# Helicopter_Control_Board.net
KiCad netlist of a schematic drawn in EAGLE
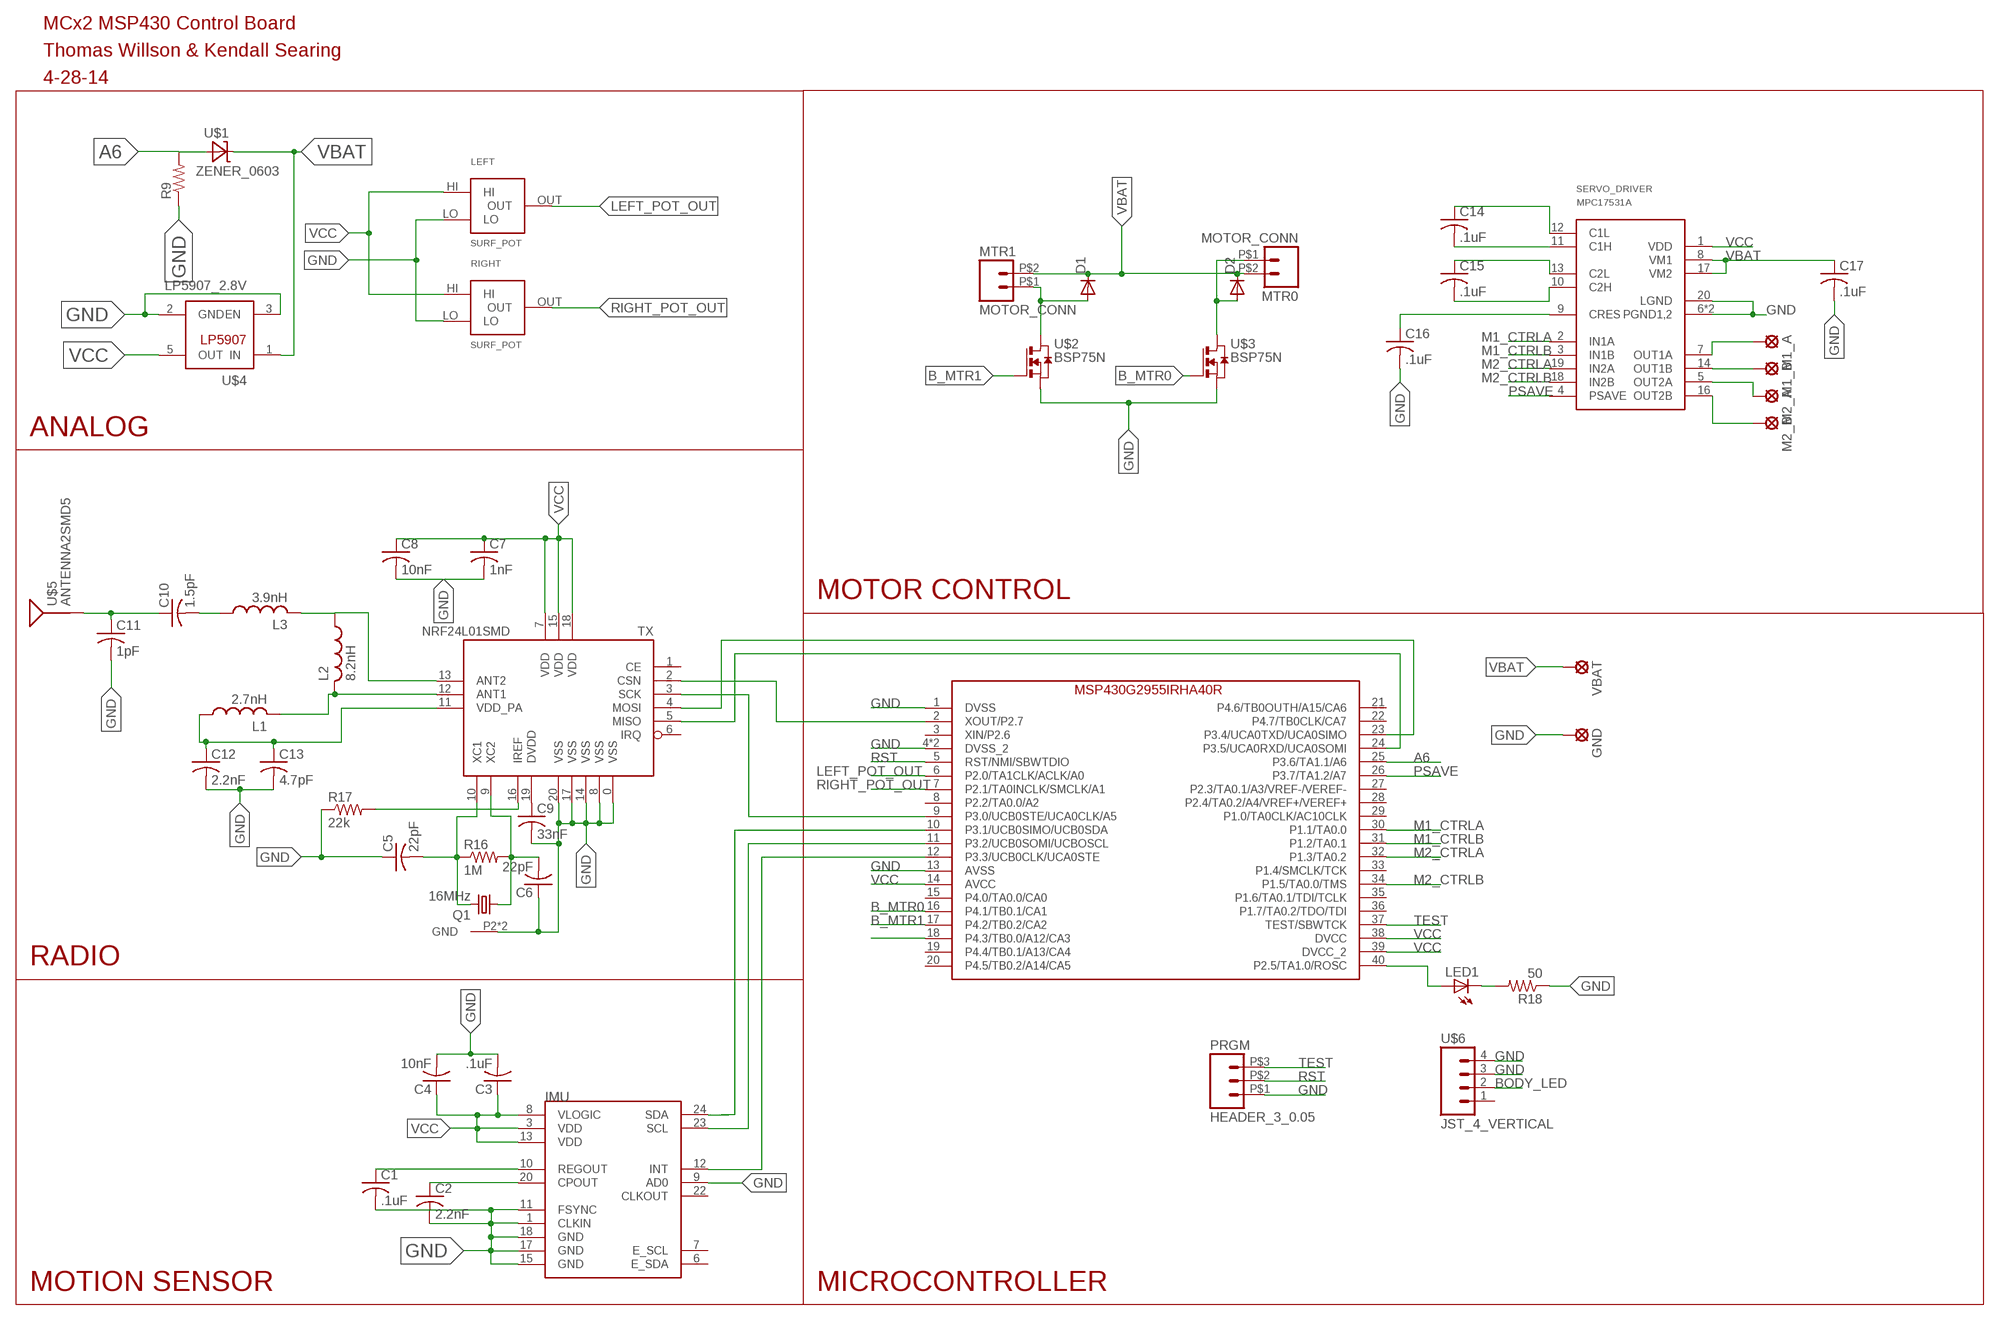
[diagram p0: schematic, sheet 1]

(export (version "E")
  (design (tool "Eeschema 10.0.6"))
  (components
    (comp (ref "C1")
      (value ".1uF")
      (footprint "eagle-import:C0402")
      (libsource (lib "eagle-import") (part "C-USC0402"))
    )
    (comp (ref "C2")
      (value "2.2nF")
      (footprint "eagle-import:C0402")
      (libsource (lib "eagle-import") (part "C-USC0402"))
    )
    (comp (ref "C3")
      (value ".1uF")
      (footprint "eagle-import:C0402")
      (libsource (lib "eagle-import") (part "C-USC0402"))
    )
    (comp (ref "C4")
      (value "10nF")
      (footprint "eagle-import:C0402")
      (libsource (lib "eagle-import") (part "C-USC0402"))
    )
    (comp (ref "C5")
      (value "22pF")
      (footprint "eagle-import:C0402")
      (libsource (lib "eagle-import") (part "C-USC0402"))
    )
    (comp (ref "C6")
      (value "22pF")
      (footprint "eagle-import:C0402")
      (libsource (lib "eagle-import") (part "C-USC0402"))
    )
    (comp (ref "C7")
      (value "1nF")
      (footprint "eagle-import:C0402")
      (libsource (lib "eagle-import") (part "C-USC0402"))
    )
    (comp (ref "C8")
      (value "10nF")
      (footprint "eagle-import:C0402")
      (libsource (lib "eagle-import") (part "C-USC0402"))
    )
    (comp (ref "C9")
      (value "33nF")
      (footprint "eagle-import:C0402")
      (libsource (lib "eagle-import") (part "C-USC0402"))
    )
    (comp (ref "C10")
      (value "1.5pF")
      (footprint "eagle-import:C0402")
      (libsource (lib "eagle-import") (part "C-USC0402"))
    )
    (comp (ref "C11")
      (value "1pF")
      (footprint "eagle-import:C0402")
      (libsource (lib "eagle-import") (part "C-USC0402"))
    )
    (comp (ref "C12")
      (value "2.2nF")
      (footprint "eagle-import:C0402")
      (libsource (lib "eagle-import") (part "C-USC0402"))
    )
    (comp (ref "C13")
      (value "4.7pF")
      (footprint "eagle-import:C0402")
      (libsource (lib "eagle-import") (part "C-USC0402"))
    )
    (comp (ref "C14")
      (value ".1uF")
      (footprint "eagle-import:C0402")
      (libsource (lib "eagle-import") (part "C-USC0402"))
    )
    (comp (ref "C15")
      (value ".1uF")
      (footprint "eagle-import:C0402")
      (libsource (lib "eagle-import") (part "C-USC0402"))
    )
    (comp (ref "C16")
      (value ".1uF")
      (footprint "eagle-import:C0402")
      (libsource (lib "eagle-import") (part "C-USC0402"))
    )
    (comp (ref "C17")
      (value ".1uF")
      (footprint "eagle-import:C0402")
      (libsource (lib "eagle-import") (part "C-USC0402"))
    )
    (comp (ref "D1")
      (value "DIODESMA")
      (footprint "eagle-import:SMA-DIODE")
      (libsource (lib "eagle-import") (part "DIODESMA"))
    )
    (comp (ref "D2")
      (value "DIODESMA")
      (footprint "eagle-import:SMA-DIODE")
      (libsource (lib "eagle-import") (part "DIODESMA"))
    )
    (comp (ref "GND")
      (value "LSP10")
      (footprint "eagle-import:LSP10")
      (libsource (lib "eagle-import") (part "LSP10"))
    )
    (comp (ref "IMU")
      (value "MPU-9150QFN-24-NP")
      (footprint "eagle-import:QFN-24-NP")
      (libsource (lib "eagle-import") (part "MPU-9150QFN-24-NP"))
    )
    (comp (ref "L1")
      (value "2.7nH")
      (footprint "eagle-import:R0402")
      (libsource (lib "eagle-import") (part "L-US"))
    )
    (comp (ref "L2")
      (value "8.2nH")
      (footprint "eagle-import:R0402")
      (libsource (lib "eagle-import") (part "L-US"))
    )
    (comp (ref "L3")
      (value "3.9nH")
      (footprint "eagle-import:R0402")
      (libsource (lib "eagle-import") (part "L-US"))
    )
    (comp (ref "LED1")
      (value "LED-BLUE0603")
      (footprint "eagle-import:LED-0603")
      (libsource (lib "eagle-import") (part "LED-BLUE0603"))
    )
    (comp (ref "LEFT")
      (value "SURF_POT")
      (footprint "eagle-import:SURF_POT")
      (libsource (lib "eagle-import") (part "SURF_POT"))
    )
    (comp (ref "M1_A")
      (value "LSP10")
      (footprint "eagle-import:LSP10")
      (libsource (lib "eagle-import") (part "LSP10"))
    )
    (comp (ref "M1_B")
      (value "LSP10")
      (footprint "eagle-import:LSP10")
      (libsource (lib "eagle-import") (part "LSP10"))
    )
    (comp (ref "M2_A")
      (value "LSP10")
      (footprint "eagle-import:LSP10")
      (libsource (lib "eagle-import") (part "LSP10"))
    )
    (comp (ref "M2_B")
      (value "LSP10")
      (footprint "eagle-import:LSP10")
      (libsource (lib "eagle-import") (part "LSP10"))
    )
    (comp (ref "MTR0")
      (value "MOTOR_CONN")
      (footprint "eagle-import:MOTOR_CONN")
      (libsource (lib "eagle-import") (part "MOTOR_CONN"))
    )
    (comp (ref "MTR1")
      (value "MOTOR_CONN")
      (footprint "eagle-import:MOTOR_CONN")
      (libsource (lib "eagle-import") (part "MOTOR_CONN"))
    )
    (comp (ref "PRGM")
      (value "HEADER_3_0.05")
      (footprint "eagle-import:HEADER_3_.05")
      (libsource (lib "eagle-import") (part "HEADER_3_0.05"))
    )
    (comp (ref "Q1")
      (value "16MHz")
      (footprint "eagle-import:TXC-4SMD")
      (libsource (lib "eagle-import") (part "CRYSTAL_16MHZ_12PF_SMD"))
    )
    (comp (ref "R9")
      (value "R-US_R0402")
      (footprint "eagle-import:R0402")
      (libsource (lib "eagle-import") (part "R-US_R0402"))
    )
    (comp (ref "R16")
      (value "1M")
      (footprint "eagle-import:R0402")
      (libsource (lib "eagle-import") (part "R-US_R0402"))
    )
    (comp (ref "R17")
      (value "22k")
      (footprint "eagle-import:R0402")
      (libsource (lib "eagle-import") (part "R-US_R0402"))
    )
    (comp (ref "R18")
      (value "50")
      (footprint "eagle-import:R0603")
      (libsource (lib "eagle-import") (part "R-US_R0603"))
    )
    (comp (ref "RIGHT")
      (value "SURF_POT")
      (footprint "eagle-import:SURF_POT")
      (libsource (lib "eagle-import") (part "SURF_POT"))
    )
    (comp (ref "SERVO_DRIVER")
      (value "MPC17531A")
      (footprint "eagle-import:SSOP_20")
      (libsource (lib "eagle-import") (part "MPC17531A"))
    )
    (comp (ref "TX")
      (value "NRF24L01SMD")
      (footprint "eagle-import:QFN20")
      (libsource (lib "eagle-import") (part "NRF24L01SMD"))
    )
    (comp (ref "U$1")
      (value "ZENER_0603")
      (footprint "eagle-import:ZENER_0603")
      (libsource (lib "eagle-import") (part "ZENER_0603"))
    )
    (comp (ref "U$2")
      (value "BSP75N")
      (footprint "eagle-import:PG-SOT-223")
      (libsource (lib "eagle-import") (part "BSP75N"))
    )
    (comp (ref "U$3")
      (value "BSP75N")
      (footprint "eagle-import:PG-SOT-223")
      (libsource (lib "eagle-import") (part "BSP75N"))
    )
    (comp (ref "U$4")
      (value "LP5907_2.8V")
      (footprint "eagle-import:SOT23-DBV")
      (libsource (lib "eagle-import") (part "LP5907"))
    )
    (comp (ref "U$5")
      (value "ANTENNA2SMD5")
      (footprint "eagle-import:ANTENNA-CHIP5")
      (libsource (lib "eagle-import") (part "ANTENNA2SMD5"))
    )
    (comp (ref "U$6")
      (value "JST_4_VERTICAL")
      (footprint "eagle-import:JST-4-SMD-VERT-1.0MM")
      (libsource (lib "eagle-import") (part "JST_4_VERTICAL"))
    )
    (comp (ref "U$8")
      (value "G2955IRHA40R")
      (footprint "eagle-import:RHA40")
      (libsource (lib "eagle-import") (part "G2955IRHA40R"))
    )
    (comp (ref "VBAT")
      (value "LSP10")
      (footprint "eagle-import:LSP10")
      (libsource (lib "eagle-import") (part "LSP10"))
    )
  )
  (nets
    (net (code "1") (name "/BODY_LED") (class "Default")
      (node (ref "U$6") (pin "2") (pinfunction "2_2") (pintype "passive"))
      (node (ref "U$8") (pin "18") (pinfunction "P4.3/TB0.0/A12/CA3_18") (pintype "bidirectional"))
    )
    (net (code "2") (name "/M1_CTRLA") (class "Default")
      (node (ref "SERVO_DRIVER") (pin "2") (pinfunction "IN1A_2") (pintype "bidirectional"))
      (node (ref "U$8") (pin "30") (pinfunction "P1.1/TA0.0_30") (pintype "bidirectional"))
    )
    (net (code "3") (name "/M1_CTRLB") (class "Default")
      (node (ref "SERVO_DRIVER") (pin "3") (pinfunction "IN1B_3") (pintype "bidirectional"))
      (node (ref "U$8") (pin "31") (pinfunction "P1.2/TA0.1_31") (pintype "bidirectional"))
    )
    (net (code "4") (name "/M2_CTRLA") (class "Default")
      (node (ref "SERVO_DRIVER") (pin "19") (pinfunction "IN2A_19") (pintype "bidirectional"))
      (node (ref "U$8") (pin "32") (pinfunction "P1.3/TA0.2_32") (pintype "bidirectional"))
    )
    (net (code "5") (name "/M2_CTRLB") (class "Default")
      (node (ref "SERVO_DRIVER") (pin "18") (pinfunction "IN2B_18") (pintype "bidirectional"))
      (node (ref "U$8") (pin "34") (pinfunction "P1.5/TA0.0/TMS_34") (pintype "bidirectional"))
    )
    (net (code "6") (name "/N$20") (class "Default")
      (node (ref "IMU") (pin "24") (pinfunction "SDA_24") (pintype "bidirectional"))
      (node (ref "U$8") (pin "10") (pinfunction "P3.1/UCB0SIMO/UCB0SDA_10") (pintype "bidirectional"))
    )
    (net (code "7") (name "/PSAVE") (class "Default")
      (node (ref "SERVO_DRIVER") (pin "4") (pinfunction "PSAVE_4") (pintype "bidirectional"))
      (node (ref "U$8") (pin "26") (pinfunction "P3.7/TA1.2/A7_26") (pintype "bidirectional"))
    )
    (net (code "8") (name "/RST") (class "Default")
      (node (ref "PRGM") (pin "P$2") (pinfunction "2_P$2") (pintype "passive"))
      (node (ref "U$8") (pin "5") (pinfunction "RST/NMI/SBWTDIO_5") (pintype "bidirectional"))
    )
    (net (code "9") (name "/TEST") (class "Default")
      (node (ref "PRGM") (pin "P$3") (pinfunction "3_P$3") (pintype "passive"))
      (node (ref "U$8") (pin "37") (pinfunction "TEST/SBWTCK_37") (pintype "bidirectional"))
    )
    (net (code "10") (name "A6") (class "Default")
      (node (ref "R9") (pin "2") (pinfunction "2_2") (pintype "passive"))
      (node (ref "U$1") (pin "A") (pinfunction "A_A") (pintype "passive"))
      (node (ref "U$8") (pin "25") (pinfunction "P3.6/TA1.1/A6_25") (pintype "bidirectional"))
    )
    (net (code "11") (name "B_MTR0") (class "Default")
      (node (ref "U$3") (pin "1") (pinfunction "G_1") (pintype "passive"))
      (node (ref "U$8") (pin "16") (pinfunction "P4.1/TB0.1/CA1_16") (pintype "bidirectional"))
    )
    (net (code "12") (name "B_MTR1") (class "Default")
      (node (ref "U$2") (pin "1") (pinfunction "G_1") (pintype "passive"))
      (node (ref "U$8") (pin "17") (pinfunction "P4.2/TB0.2/CA2_17") (pintype "bidirectional"))
    )
    (net (code "13") (name "GND") (class "Default")
      (node (ref "C1") (pin "2") (pinfunction "2_2") (pintype "passive"))
      (node (ref "C11") (pin "2") (pinfunction "2_2") (pintype "passive"))
      (node (ref "C12") (pin "2") (pinfunction "2_2") (pintype "passive"))
      (node (ref "C13") (pin "2") (pinfunction "2_2") (pintype "passive"))
      (node (ref "C16") (pin "2") (pinfunction "2_2") (pintype "passive"))
      (node (ref "C17") (pin "2") (pinfunction "2_2") (pintype "passive"))
      (node (ref "C2") (pin "2") (pinfunction "2_2") (pintype "passive"))
      (node (ref "C3") (pin "2") (pinfunction "2_2") (pintype "passive"))
      (node (ref "C4") (pin "2") (pinfunction "2_2") (pintype "passive"))
      (node (ref "C5") (pin "1") (pinfunction "1_1") (pintype "passive"))
      (node (ref "C6") (pin "1") (pinfunction "1_1") (pintype "passive"))
      (node (ref "C7") (pin "2") (pinfunction "2_2") (pintype "passive"))
      (node (ref "C8") (pin "2") (pinfunction "2_2") (pintype "passive"))
      (node (ref "C9") (pin "2") (pinfunction "2_2") (pintype "passive"))
      (node (ref "GND") (pin "MP") (pinfunction "MP_MP") (pintype "passive"))
      (node (ref "IMU") (pin "1") (pinfunction "CLKIN_1") (pintype "bidirectional"))
      (node (ref "IMU") (pin "11") (pinfunction "FSYNC_11") (pintype "bidirectional"))
      (node (ref "IMU") (pin "15") (pinfunction "GND_15") (pintype "bidirectional"))
      (node (ref "IMU") (pin "17") (pinfunction "GND_17") (pintype "bidirectional"))
      (node (ref "IMU") (pin "18") (pinfunction "GND_18") (pintype "bidirectional"))
      (node (ref "IMU") (pin "9") (pinfunction "AD0_9") (pintype "bidirectional"))
      (node (ref "LEFT") (pin "LO") (pinfunction "LO_LO") (pintype "bidirectional"))
      (node (ref "PRGM") (pin "P$1") (pinfunction "1_P$1") (pintype "passive"))
      (node (ref "Q1") (pin "P2") (pinfunction "GND_P2") (pintype "bidirectional"))
      (node (ref "Q1") (pin "P4") (pinfunction "GND_P4") (pintype "bidirectional"))
      (node (ref "R17") (pin "1") (pinfunction "1_1") (pintype "passive"))
      (node (ref "R18") (pin "1") (pinfunction "1_1") (pintype "passive"))
      (node (ref "R9") (pin "1") (pinfunction "1_1") (pintype "passive"))
      (node (ref "RIGHT") (pin "LO") (pinfunction "LO_LO") (pintype "bidirectional"))
      (node (ref "SERVO_DRIVER") (pin "15") (pinfunction "PGND1,2_15") (pintype "bidirectional"))
      (node (ref "SERVO_DRIVER") (pin "20") (pinfunction "LGND_20") (pintype "bidirectional"))
      (node (ref "SERVO_DRIVER") (pin "6") (pinfunction "PGND1,2_6") (pintype "bidirectional"))
      (node (ref "TX") (pin "0") (pinfunction "VSS_0") (pintype "power_in"))
      (node (ref "TX") (pin "14") (pinfunction "VSS_14") (pintype "power_in"))
      (node (ref "TX") (pin "17") (pinfunction "VSS_17") (pintype "power_in"))
      (node (ref "TX") (pin "20") (pinfunction "VSS_20") (pintype "power_in"))
      (node (ref "TX") (pin "8") (pinfunction "VSS_8") (pintype "power_in"))
      (node (ref "U$2") (pin "3") (pinfunction "S_3") (pintype "passive"))
      (node (ref "U$2") (pin "4") (pinfunction "S_4") (pintype "passive"))
      (node (ref "U$3") (pin "3") (pinfunction "S_3") (pintype "passive"))
      (node (ref "U$3") (pin "4") (pinfunction "S_4") (pintype "passive"))
      (node (ref "U$4") (pin "2") (pinfunction "GND_2") (pintype "bidirectional"))
      (node (ref "U$4") (pin "3") (pinfunction "EN_3") (pintype "bidirectional"))
      (node (ref "U$6") (pin "3") (pinfunction "3_3") (pintype "passive"))
      (node (ref "U$6") (pin "4") (pinfunction "4_4") (pintype "passive"))
      (node (ref "U$8") (pin "1") (pinfunction "DVSS_1") (pintype "bidirectional"))
      (node (ref "U$8") (pin "13") (pinfunction "AVSS_13") (pintype "bidirectional"))
      (node (ref "U$8") (pin "4") (pinfunction "DVSS_2_4") (pintype "bidirectional"))
      (node (ref "U$8") (pin "TP") (pinfunction "DVSS_2_TP") (pintype "bidirectional"))
    )
    (net (code "14") (name "LEFT_POT_OUT") (class "Default")
      (node (ref "LEFT") (pin "OUT") (pinfunction "OUT_OUT") (pintype "bidirectional"))
      (node (ref "U$8") (pin "6") (pinfunction "P2.0/TA1CLK/ACLK/A0_6") (pintype "bidirectional"))
    )
    (net (code "15") (name "Net-(C10-Pad2)") (class "Default")
      (node (ref "C10") (pin "2") (pinfunction "2_2") (pintype "passive"))
      (node (ref "L3") (pin "1") (pinfunction "1_1") (pintype "passive"))
    )
    (net (code "16") (name "Net-(IMU-CPOUT)") (class "Default")
      (node (ref "C2") (pin "1") (pinfunction "1_1") (pintype "passive"))
      (node (ref "IMU") (pin "20") (pinfunction "CPOUT_20") (pintype "bidirectional"))
    )
    (net (code "17") (name "Net-(IMU-INT)") (class "Default")
      (node (ref "IMU") (pin "12") (pinfunction "INT_12") (pintype "bidirectional"))
      (node (ref "U$8") (pin "12") (pinfunction "P3.3/UCB0CLK/UCA0STE_12") (pintype "bidirectional"))
    )
    (net (code "18") (name "Net-(IMU-REGOUT)") (class "Default")
      (node (ref "C1") (pin "1") (pinfunction "1_1") (pintype "passive"))
      (node (ref "IMU") (pin "10") (pinfunction "REGOUT_10") (pintype "bidirectional"))
    )
    (net (code "19") (name "Net-(IMU-SCL)") (class "Default")
      (node (ref "IMU") (pin "23") (pinfunction "SCL_23") (pintype "bidirectional"))
      (node (ref "U$8") (pin "11") (pinfunction "P3.2/UCB0SOMI/UCBOSCL_11") (pintype "bidirectional"))
    )
    (net (code "20") (name "Net-(LED1-PadC)") (class "Default")
      (node (ref "LED1") (pin "C") (pinfunction "C_C") (pintype "passive"))
      (node (ref "R18") (pin "2") (pinfunction "2_2") (pintype "passive"))
    )
    (net (code "21") (name "Net-(MTR0-1)") (class "Default")
      (node (ref "D2") (pin "A") (pinfunction "A_A") (pintype "passive"))
      (node (ref "MTR0") (pin "P$1") (pinfunction "1_P$1") (pintype "passive"))
      (node (ref "U$3") (pin "2") (pinfunction "D_2") (pintype "passive"))
    )
    (net (code "22") (name "Net-(MTR1-1)") (class "Default")
      (node (ref "D1") (pin "A") (pinfunction "A_A") (pintype "passive"))
      (node (ref "MTR1") (pin "P$1") (pinfunction "1_P$1") (pintype "passive"))
      (node (ref "U$2") (pin "2") (pinfunction "D_2") (pintype "passive"))
    )
    (net (code "23") (name "Net-(Q1-1)") (class "Default")
      (node (ref "C6") (pin "2") (pinfunction "2_2") (pintype "passive"))
      (node (ref "Q1") (pin "P1") (pinfunction "1_P1") (pintype "passive"))
      (node (ref "R16") (pin "2") (pinfunction "2_2") (pintype "passive"))
    )
    (net (code "24") (name "Net-(Q1-2)") (class "Default")
      (node (ref "C5") (pin "2") (pinfunction "2_2") (pintype "passive"))
      (node (ref "Q1") (pin "P3") (pinfunction "2_P3") (pintype "passive"))
      (node (ref "R16") (pin "1") (pinfunction "1_1") (pintype "passive"))
      (node (ref "TX") (pin "10") (pinfunction "XC1_10") (pintype "input"))
    )
    (net (code "25") (name "Net-(SERVO_DRIVER-C1H)") (class "Default")
      (node (ref "C14") (pin "2") (pinfunction "2_2") (pintype "passive"))
      (node (ref "SERVO_DRIVER") (pin "11") (pinfunction "C1H_11") (pintype "bidirectional"))
    )
    (net (code "26") (name "Net-(SERVO_DRIVER-C1L)") (class "Default")
      (node (ref "C14") (pin "1") (pinfunction "1_1") (pintype "passive"))
      (node (ref "SERVO_DRIVER") (pin "12") (pinfunction "C1L_12") (pintype "bidirectional"))
    )
    (net (code "27") (name "Net-(SERVO_DRIVER-C2H)") (class "Default")
      (node (ref "C15") (pin "2") (pinfunction "2_2") (pintype "passive"))
      (node (ref "SERVO_DRIVER") (pin "10") (pinfunction "C2H_10") (pintype "bidirectional"))
    )
    (net (code "28") (name "Net-(SERVO_DRIVER-C2L)") (class "Default")
      (node (ref "C15") (pin "1") (pinfunction "1_1") (pintype "passive"))
      (node (ref "SERVO_DRIVER") (pin "13") (pinfunction "C2L_13") (pintype "bidirectional"))
    )
    (net (code "29") (name "Net-(SERVO_DRIVER-CRES)") (class "Default")
      (node (ref "C16") (pin "1") (pinfunction "1_1") (pintype "passive"))
      (node (ref "SERVO_DRIVER") (pin "9") (pinfunction "CRES_9") (pintype "bidirectional"))
    )
    (net (code "30") (name "Net-(SERVO_DRIVER-OUT1A)") (class "Default")
      (node (ref "M1_A") (pin "MP") (pinfunction "MP_MP") (pintype "passive"))
      (node (ref "SERVO_DRIVER") (pin "7") (pinfunction "OUT1A_7") (pintype "bidirectional"))
    )
    (net (code "31") (name "Net-(SERVO_DRIVER-OUT1B)") (class "Default")
      (node (ref "M1_B") (pin "MP") (pinfunction "MP_MP") (pintype "passive"))
      (node (ref "SERVO_DRIVER") (pin "14") (pinfunction "OUT1B_14") (pintype "bidirectional"))
    )
    (net (code "32") (name "Net-(SERVO_DRIVER-OUT2A)") (class "Default")
      (node (ref "M2_A") (pin "MP") (pinfunction "MP_MP") (pintype "passive"))
      (node (ref "SERVO_DRIVER") (pin "5") (pinfunction "OUT2A_5") (pintype "bidirectional"))
    )
    (net (code "33") (name "Net-(SERVO_DRIVER-OUT2B)") (class "Default")
      (node (ref "M2_B") (pin "MP") (pinfunction "MP_MP") (pintype "passive"))
      (node (ref "SERVO_DRIVER") (pin "16") (pinfunction "OUT2B_16") (pintype "bidirectional"))
    )
    (net (code "34") (name "Net-(TX-ANT1)") (class "Default")
      (node (ref "L1") (pin "2") (pinfunction "2_2") (pintype "passive"))
      (node (ref "L2") (pin "2") (pinfunction "2_2") (pintype "passive"))
      (node (ref "TX") (pin "12") (pinfunction "ANT1_12") (pintype "output"))
    )
    (net (code "35") (name "Net-(TX-ANT2)") (class "Default")
      (node (ref "L2") (pin "1") (pinfunction "1_1") (pintype "passive"))
      (node (ref "L3") (pin "2") (pinfunction "2_2") (pintype "passive"))
      (node (ref "TX") (pin "13") (pinfunction "ANT2_13") (pintype "output"))
    )
    (net (code "36") (name "Net-(TX-CSN)") (class "Default")
      (node (ref "TX") (pin "2") (pinfunction "CSN_2") (pintype "input"))
      (node (ref "U$8") (pin "2") (pinfunction "XOUT/P2.7_2") (pintype "bidirectional"))
    )
    (net (code "37") (name "Net-(TX-DVDD)") (class "Default")
      (node (ref "C9") (pin "1") (pinfunction "1_1") (pintype "passive"))
      (node (ref "TX") (pin "19") (pinfunction "DVDD_19") (pintype "power_in"))
    )
    (net (code "38") (name "Net-(TX-IREF)") (class "Default")
      (node (ref "R17") (pin "2") (pinfunction "2_2") (pintype "passive"))
      (node (ref "TX") (pin "16") (pinfunction "IREF_16") (pintype "input"))
    )
    (net (code "39") (name "Net-(TX-MISO)") (class "Default")
      (node (ref "TX") (pin "5") (pinfunction "MISO_5") (pintype "output"))
      (node (ref "U$8") (pin "24") (pinfunction "P3.5/UCA0RXD/UCA0SOMI_24") (pintype "bidirectional"))
    )
    (net (code "40") (name "Net-(TX-MOSI)") (class "Default")
      (node (ref "TX") (pin "4") (pinfunction "MOSI_4") (pintype "input"))
      (node (ref "U$8") (pin "23") (pinfunction "P3.4/UCA0TXD/UCA0SIMO_23") (pintype "bidirectional"))
    )
    (net (code "41") (name "Net-(TX-SCK)") (class "Default")
      (node (ref "TX") (pin "3") (pinfunction "SCK_3") (pintype "input"))
      (node (ref "U$8") (pin "9") (pinfunction "P3.0/UCB0STE/UCA0CLK/A5_9") (pintype "bidirectional"))
    )
    (net (code "42") (name "Net-(TX-VDD_PA)") (class "Default")
      (node (ref "C12") (pin "1") (pinfunction "1_1") (pintype "passive"))
      (node (ref "C13") (pin "1") (pinfunction "1_1") (pintype "passive"))
      (node (ref "L1") (pin "1") (pinfunction "1_1") (pintype "passive"))
      (node (ref "TX") (pin "11") (pinfunction "VDD_PA_11") (pintype "power_in"))
    )
    (net (code "43") (name "Net-(U$5-SIGNAL)") (class "Default")
      (node (ref "C10") (pin "1") (pinfunction "1_1") (pintype "passive"))
      (node (ref "C11") (pin "1") (pinfunction "1_1") (pintype "passive"))
      (node (ref "U$5") (pin "FEED") (pinfunction "SIGNAL_FEED") (pintype "bidirectional"))
    )
    (net (code "44") (name "Net-(U$8-P2.5{slash}TA1.0{slash}ROSC)") (class "Default")
      (node (ref "LED1") (pin "A") (pinfunction "A_A") (pintype "passive"))
      (node (ref "U$8") (pin "40") (pinfunction "P2.5/TA1.0/ROSC_40") (pintype "bidirectional"))
    )
    (net (code "45") (name "RIGHT_POT_OUT") (class "Default")
      (node (ref "RIGHT") (pin "OUT") (pinfunction "OUT_OUT") (pintype "bidirectional"))
      (node (ref "U$8") (pin "7") (pinfunction "P2.1/TA0INCLK/SMCLK/A1_7") (pintype "bidirectional"))
    )
    (net (code "46") (name "VBAT") (class "Default")
      (node (ref "C17") (pin "1") (pinfunction "1_1") (pintype "passive"))
      (node (ref "D1") (pin "C") (pinfunction "C_C") (pintype "passive"))
      (node (ref "D2") (pin "C") (pinfunction "C_C") (pintype "passive"))
      (node (ref "MTR0") (pin "P$2") (pinfunction "2_P$2") (pintype "passive"))
      (node (ref "MTR1") (pin "P$2") (pinfunction "2_P$2") (pintype "passive"))
      (node (ref "SERVO_DRIVER") (pin "17") (pinfunction "VM2_17") (pintype "bidirectional"))
      (node (ref "SERVO_DRIVER") (pin "8") (pinfunction "VM1_8") (pintype "bidirectional"))
      (node (ref "U$1") (pin "C") (pinfunction "C_C") (pintype "passive"))
      (node (ref "U$4") (pin "1") (pinfunction "IN_1") (pintype "bidirectional"))
      (node (ref "VBAT") (pin "MP") (pinfunction "MP_MP") (pintype "passive"))
    )
    (net (code "47") (name "VCC") (class "Default")
      (node (ref "C3") (pin "1") (pinfunction "1_1") (pintype "passive"))
      (node (ref "C4") (pin "1") (pinfunction "1_1") (pintype "passive"))
      (node (ref "C7") (pin "1") (pinfunction "1_1") (pintype "passive"))
      (node (ref "C8") (pin "1") (pinfunction "1_1") (pintype "passive"))
      (node (ref "IMU") (pin "13") (pinfunction "VDD_13") (pintype "bidirectional"))
      (node (ref "IMU") (pin "3") (pinfunction "VDD_3") (pintype "bidirectional"))
      (node (ref "IMU") (pin "8") (pinfunction "VLOGIC_8") (pintype "bidirectional"))
      (node (ref "LEFT") (pin "HI") (pinfunction "HI_HI") (pintype "bidirectional"))
      (node (ref "RIGHT") (pin "HI") (pinfunction "HI_HI") (pintype "bidirectional"))
      (node (ref "SERVO_DRIVER") (pin "1") (pinfunction "VDD_1") (pintype "bidirectional"))
      (node (ref "TX") (pin "15") (pinfunction "VDD_15") (pintype "power_in"))
      (node (ref "TX") (pin "18") (pinfunction "VDD_18") (pintype "power_in"))
      (node (ref "TX") (pin "7") (pinfunction "VDD_7") (pintype "power_in"))
      (node (ref "U$4") (pin "5") (pinfunction "OUT_5") (pintype "bidirectional"))
      (node (ref "U$8") (pin "14") (pinfunction "AVCC_14") (pintype "bidirectional"))
      (node (ref "U$8") (pin "38") (pinfunction "DVCC_38") (pintype "bidirectional"))
      (node (ref "U$8") (pin "39") (pinfunction "DVCC_2_39") (pintype "bidirectional"))
    )
    (net (code "48") (name "unconnected-(IMU-CLKOUT-Pad22)") (class "Default")
      (node (ref "IMU") (pin "22") (pinfunction "CLKOUT_22") (pintype "bidirectional"))
    )
    (net (code "49") (name "unconnected-(IMU-E_SCL-Pad7)") (class "Default")
      (node (ref "IMU") (pin "7") (pinfunction "E_SCL_7") (pintype "bidirectional"))
    )
    (net (code "50") (name "unconnected-(IMU-E_SDA-Pad6)") (class "Default")
      (node (ref "IMU") (pin "6") (pinfunction "E_SDA_6") (pintype "bidirectional"))
    )
    (net (code "51") (name "unconnected-(TX-CE-Pad1)") (class "Default")
      (node (ref "TX") (pin "1") (pinfunction "CE_1") (pintype "input"))
    )
    (net (code "52") (name "unconnected-(TX-IRQ-Pad6)") (class "Default")
      (node (ref "TX") (pin "6") (pinfunction "IRQ_6") (pintype "output"))
    )
    (net (code "53") (name "unconnected-(TX-XC2-Pad9)") (class "Default")
      (node (ref "TX") (pin "9") (pinfunction "XC2_9") (pintype "input"))
    )
    (net (code "54") (name "unconnected-(U$6-Pad1)") (class "Default")
      (node (ref "U$6") (pin "1") (pinfunction "1_1") (pintype "passive"))
    )
    (net (code "55") (name "unconnected-(U$8-P1.0{slash}TA0CLK{slash}AC10CLK-Pad29)") (class "Default")
      (node (ref "U$8") (pin "29") (pinfunction "P1.0/TA0CLK/AC10CLK_29") (pintype "bidirectional"))
    )
    (net (code "56") (name "unconnected-(U$8-P1.4{slash}SMCLK{slash}TCK-Pad33)") (class "Default")
      (node (ref "U$8") (pin "33") (pinfunction "P1.4/SMCLK/TCK_33") (pintype "bidirectional"))
    )
    (net (code "57") (name "unconnected-(U$8-P1.6{slash}TA0.1{slash}TDI{slash}TCLK-Pad35)") (class "Default")
      (node (ref "U$8") (pin "35") (pinfunction "P1.6/TA0.1/TDI/TCLK_35") (pintype "bidirectional"))
    )
    (net (code "58") (name "unconnected-(U$8-P1.7{slash}TA0.2{slash}TDO{slash}TDI-Pad36)") (class "Default")
      (node (ref "U$8") (pin "36") (pinfunction "P1.7/TA0.2/TDO/TDI_36") (pintype "bidirectional"))
    )
    (net (code "59") (name "unconnected-(U$8-P2.2{slash}TA0.0{slash}A2-Pad8)") (class "Default")
      (node (ref "U$8") (pin "8") (pinfunction "P2.2/TA0.0/A2_8") (pintype "bidirectional"))
    )
    (net (code "60") (name "unconnected-(U$8-P2.3{slash}TA0.1{slash}A3{slash}VREF-{slash}VEREF--Pad27)") (class "Default")
      (node (ref "U$8") (pin "27") (pinfunction "P2.3/TA0.1/A3/VREF-/VEREF-_27") (pintype "bidirectional"))
    )
    (net (code "61") (name "unconnected-(U$8-P2.4{slash}TA0.2{slash}A4{slash}VREF+{slash}VEREF+-Pad28)") (class "Default")
      (node (ref "U$8") (pin "28") (pinfunction "P2.4/TA0.2/A4/VREF+/VEREF+_28") (pintype "bidirectional"))
    )
    (net (code "62") (name "unconnected-(U$8-P4.0{slash}TA0.0{slash}CA0-Pad15)") (class "Default")
      (node (ref "U$8") (pin "15") (pinfunction "P4.0/TA0.0/CA0_15") (pintype "bidirectional"))
    )
    (net (code "63") (name "unconnected-(U$8-P4.4{slash}TB0.1{slash}A13{slash}CA4-Pad19)") (class "Default")
      (node (ref "U$8") (pin "19") (pinfunction "P4.4/TB0.1/A13/CA4_19") (pintype "bidirectional"))
    )
    (net (code "64") (name "unconnected-(U$8-P4.5{slash}TB0.2{slash}A14{slash}CA5-Pad20)") (class "Default")
      (node (ref "U$8") (pin "20") (pinfunction "P4.5/TB0.2/A14/CA5_20") (pintype "bidirectional"))
    )
    (net (code "65") (name "unconnected-(U$8-P4.6{slash}TB0OUTH{slash}A15{slash}CA6-Pad21)") (class "Default")
      (node (ref "U$8") (pin "21") (pinfunction "P4.6/TB0OUTH/A15/CA6_21") (pintype "bidirectional"))
    )
    (net (code "66") (name "unconnected-(U$8-P4.7{slash}TB0CLK{slash}CA7-Pad22)") (class "Default")
      (node (ref "U$8") (pin "22") (pinfunction "P4.7/TB0CLK/CA7_22") (pintype "bidirectional"))
    )
    (net (code "67") (name "unconnected-(U$8-XIN{slash}P2.6-Pad3)") (class "Default")
      (node (ref "U$8") (pin "3") (pinfunction "XIN/P2.6_3") (pintype "bidirectional"))
    )
  )
)
